# Alfa_t.net
KiCad netlist of a schematic drawn in EAGLE
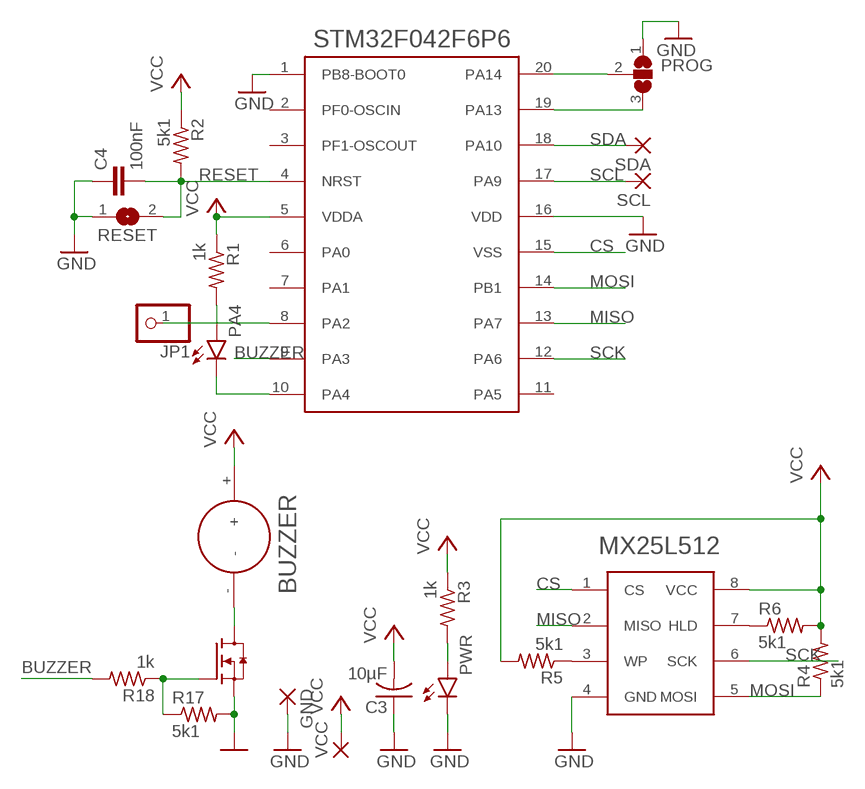
[diagram p0: schematic, sheet 1]

(export (version "E")
  (design (tool "Eeschema 10.0.6"))
  (components
    (comp (ref "BUZ")
      (value "SI2302CDS")
      (footprint "eagle-import:SOT23-3")
      (libsource (lib "eagle-import") (part "SI2302CDS"))
    )
    (comp (ref "BUZZER")
      (value "BUZZER-5V")
      (footprint "eagle-import:BUZZER")
      (libsource (lib "eagle-import") (part "BUZZER-5V"))
    )
    (comp (ref "C3")
      (value "10µF")
      (footprint "eagle-import:C1206")
      (libsource (lib "eagle-import") (part "C-USC1206"))
    )
    (comp (ref "C4")
      (value "100nF")
      (footprint "eagle-import:C0603")
      (libsource (lib "eagle-import") (part "C-EUC0603"))
    )
    (comp (ref "GND")
      (value "SMD2")
      (footprint "eagle-import:SMD1,27-2,54")
      (libsource (lib "eagle-import") (part "SMD2"))
    )
    (comp (ref "JP1")
      (value "PINHD-1X1")
      (footprint "eagle-import:1X01")
      (libsource (lib "eagle-import") (part "PINHD-1X1"))
    )
    (comp (ref "MX25L512")
      (value "MX25L25645")
      (footprint "eagle-import:SOP8")
      (libsource (lib "eagle-import") (part "MX25L25645"))
    )
    (comp (ref "PA4")
      (value "LEDCHIPLED_0603")
      (footprint "eagle-import:CHIPLED_0603")
      (libsource (lib "eagle-import") (part "LEDCHIPLED_0603"))
    )
    (comp (ref "PROG")
      (value "SJ2W")
      (footprint "eagle-import:SJ_2")
      (libsource (lib "eagle-import") (part "SJ2W"))
    )
    (comp (ref "PWR")
      (value "LEDCHIPLED_0603")
      (footprint "eagle-import:CHIPLED_0603")
      (libsource (lib "eagle-import") (part "LEDCHIPLED_0603"))
    )
    (comp (ref "R1")
      (value "1k")
      (footprint "eagle-import:R0603")
      (libsource (lib "eagle-import") (part "R-US_R0603"))
    )
    (comp (ref "R2")
      (value "5k1")
      (footprint "eagle-import:R0603")
      (libsource (lib "eagle-import") (part "R-US_R0603"))
    )
    (comp (ref "R3")
      (value "1k")
      (footprint "eagle-import:R0603")
      (libsource (lib "eagle-import") (part "R-US_R0603"))
    )
    (comp (ref "R4")
      (value "5k1")
      (footprint "eagle-import:R0603")
      (libsource (lib "eagle-import") (part "R-US_R0603"))
    )
    (comp (ref "R5")
      (value "5k1")
      (footprint "eagle-import:R0603")
      (libsource (lib "eagle-import") (part "R-US_R0603"))
    )
    (comp (ref "R6")
      (value "5k1")
      (footprint "eagle-import:R0603")
      (libsource (lib "eagle-import") (part "R-US_R0603"))
    )
    (comp (ref "R17")
      (value "5k1")
      (footprint "eagle-import:R0603")
      (libsource (lib "eagle-import") (part "R-US_R0603"))
    )
    (comp (ref "R18")
      (value "1k")
      (footprint "eagle-import:R0603")
      (libsource (lib "eagle-import") (part "R-US_R0603"))
    )
    (comp (ref "RESET")
      (value "SJ")
      (footprint "eagle-import:SJ")
      (libsource (lib "eagle-import") (part "SJ"))
    )
    (comp (ref "SCL")
      (value "SMD2")
      (footprint "eagle-import:SMD1,27-2,54")
      (libsource (lib "eagle-import") (part "SMD2"))
    )
    (comp (ref "SDA")
      (value "SMD2")
      (footprint "eagle-import:SMD1,27-2,54")
      (libsource (lib "eagle-import") (part "SMD2"))
    )
    (comp (ref "STM32F042F6P6")
      (value "STM32F042F6P6")
      (footprint "eagle-import:TSSOP-20")
      (libsource (lib "eagle-import") (part "STM32F042F6P6"))
    )
    (comp (ref "VCC")
      (value "SMD2")
      (footprint "eagle-import:SMD1,27-2,54")
      (libsource (lib "eagle-import") (part "SMD2"))
    )
  )
  (nets
    (net (code "1") (name "/BUZZER") (class "Default")
      (node (ref "R18") (pin "2") (pinfunction "2_2") (pintype "passive"))
      (node (ref "STM32F042F6P6") (pin "9") (pinfunction "PA3_9") (pintype "bidirectional"))
    )
    (net (code "2") (name "/CS") (class "Default")
      (node (ref "MX25L512") (pin "1") (pinfunction "CS_1") (pintype "bidirectional"))
      (node (ref "STM32F042F6P6") (pin "15") (pinfunction "VSS_15") (pintype "bidirectional"))
    )
    (net (code "3") (name "/MISO") (class "Default")
      (node (ref "MX25L512") (pin "2") (pinfunction "MISO_2") (pintype "bidirectional"))
      (node (ref "STM32F042F6P6") (pin "13") (pinfunction "PA7_13") (pintype "bidirectional"))
    )
    (net (code "4") (name "/MOSI") (class "Default")
      (node (ref "MX25L512") (pin "5") (pinfunction "MOSI_5") (pintype "bidirectional"))
      (node (ref "R4") (pin "1") (pinfunction "1_1") (pintype "passive"))
      (node (ref "STM32F042F6P6") (pin "14") (pinfunction "PB1_14") (pintype "bidirectional"))
    )
    (net (code "5") (name "/RESET") (class "Default")
      (node (ref "C4") (pin "2") (pinfunction "2_2") (pintype "passive"))
      (node (ref "R2") (pin "2") (pinfunction "2_2") (pintype "passive"))
      (node (ref "RESET") (pin "2") (pinfunction "2_2") (pintype "passive"))
      (node (ref "STM32F042F6P6") (pin "4") (pinfunction "NRST_4") (pintype "bidirectional"))
    )
    (net (code "6") (name "/SCK") (class "Default")
      (node (ref "MX25L512") (pin "6") (pinfunction "SCK_6") (pintype "bidirectional"))
      (node (ref "STM32F042F6P6") (pin "12") (pinfunction "PA6_12") (pintype "bidirectional"))
    )
    (net (code "7") (name "/SCL") (class "Default")
      (node (ref "SCL") (pin "1") (pinfunction "P_1") (pintype "passive"))
      (node (ref "STM32F042F6P6") (pin "17") (pinfunction "PA9_17") (pintype "bidirectional"))
    )
    (net (code "8") (name "/SDA") (class "Default")
      (node (ref "SDA") (pin "1") (pinfunction "P_1") (pintype "passive"))
      (node (ref "STM32F042F6P6") (pin "18") (pinfunction "PA10_18") (pintype "bidirectional"))
    )
    (net (code "9") (name "GND") (class "Default")
      (node (ref "BUZ") (pin "2") (pinfunction "S_2") (pintype "passive"))
      (node (ref "C3") (pin "1") (pinfunction "1_1") (pintype "passive"))
      (node (ref "C4") (pin "1") (pinfunction "1_1") (pintype "passive"))
      (node (ref "GND") (pin "1") (pinfunction "P_1") (pintype "passive"))
      (node (ref "MX25L512") (pin "4") (pinfunction "GND_4") (pintype "bidirectional"))
      (node (ref "PROG") (pin "1") (pinfunction "1_1") (pintype "passive"))
      (node (ref "PWR") (pin "C") (pinfunction "C_C") (pintype "passive"))
      (node (ref "R17") (pin "2") (pinfunction "2_2") (pintype "passive"))
      (node (ref "RESET") (pin "1") (pinfunction "1_1") (pintype "passive"))
      (node (ref "STM32F042F6P6") (pin "1") (pinfunction "PB8-BOOT0_1") (pintype "bidirectional"))
      (node (ref "STM32F042F6P6") (pin "16") (pinfunction "VDD_16") (pintype "bidirectional"))
    )
    (net (code "10") (name "Net-(BUZ-D)") (class "Default")
      (node (ref "BUZ") (pin "3") (pinfunction "D_3") (pintype "passive"))
      (node (ref "BUZZER") (pin "-") (pinfunction "-_-") (pintype "bidirectional"))
    )
    (net (code "11") (name "Net-(BUZ-G)") (class "Default")
      (node (ref "BUZ") (pin "1") (pinfunction "G_1") (pintype "passive"))
      (node (ref "R17") (pin "1") (pinfunction "1_1") (pintype "passive"))
      (node (ref "R18") (pin "1") (pinfunction "1_1") (pintype "passive"))
    )
    (net (code "12") (name "Net-(MX25L512-HLD)") (class "Default")
      (node (ref "MX25L512") (pin "7") (pinfunction "HLD_7") (pintype "bidirectional"))
      (node (ref "R6") (pin "1") (pinfunction "1_1") (pintype "passive"))
    )
    (net (code "13") (name "Net-(MX25L512-WP)") (class "Default")
      (node (ref "MX25L512") (pin "3") (pinfunction "WP_3") (pintype "bidirectional"))
      (node (ref "R5") (pin "1") (pinfunction "1_1") (pintype "passive"))
    )
    (net (code "14") (name "Net-(PA4-PadA)") (class "Default")
      (node (ref "PA4") (pin "A") (pinfunction "A_A") (pintype "passive"))
      (node (ref "R1") (pin "2") (pinfunction "2_2") (pintype "passive"))
    )
    (net (code "15") (name "Net-(PWR-PadA)") (class "Default")
      (node (ref "PWR") (pin "A") (pinfunction "A_A") (pintype "passive"))
      (node (ref "R3") (pin "2") (pinfunction "2_2") (pintype "passive"))
    )
    (net (code "16") (name "Net-(STM32F042F6P6-PA2)") (class "Default")
      (node (ref "JP1") (pin "1") (pinfunction "1_1") (pintype "passive"))
      (node (ref "STM32F042F6P6") (pin "8") (pinfunction "PA2_8") (pintype "bidirectional"))
    )
    (net (code "17") (name "Net-(STM32F042F6P6-PA4)") (class "Default")
      (node (ref "PA4") (pin "C") (pinfunction "C_C") (pintype "passive"))
      (node (ref "STM32F042F6P6") (pin "10") (pinfunction "PA4_10") (pintype "bidirectional"))
    )
    (net (code "18") (name "Net-(STM32F042F6P6-PA13)") (class "Default")
      (node (ref "PROG") (pin "3") (pinfunction "3_3") (pintype "passive"))
      (node (ref "STM32F042F6P6") (pin "19") (pinfunction "PA13_19") (pintype "bidirectional"))
    )
    (net (code "19") (name "Net-(STM32F042F6P6-PA14)") (class "Default")
      (node (ref "PROG") (pin "2") (pinfunction "2_2") (pintype "passive"))
      (node (ref "STM32F042F6P6") (pin "20") (pinfunction "PA14_20") (pintype "bidirectional"))
    )
    (net (code "20") (name "VCC") (class "Default")
      (node (ref "BUZZER") (pin "+") (pinfunction "+_+") (pintype "bidirectional"))
      (node (ref "C3") (pin "2") (pinfunction "2_2") (pintype "passive"))
      (node (ref "MX25L512") (pin "8") (pinfunction "VCC_8") (pintype "bidirectional"))
      (node (ref "R1") (pin "1") (pinfunction "1_1") (pintype "passive"))
      (node (ref "R2") (pin "1") (pinfunction "1_1") (pintype "passive"))
      (node (ref "R3") (pin "1") (pinfunction "1_1") (pintype "passive"))
      (node (ref "R4") (pin "2") (pinfunction "2_2") (pintype "passive"))
      (node (ref "R5") (pin "2") (pinfunction "2_2") (pintype "passive"))
      (node (ref "R6") (pin "2") (pinfunction "2_2") (pintype "passive"))
      (node (ref "STM32F042F6P6") (pin "5") (pinfunction "VDDA_5") (pintype "bidirectional"))
      (node (ref "VCC") (pin "1") (pinfunction "P_1") (pintype "passive"))
    )
    (net (code "21") (name "unconnected-(STM32F042F6P6-PA0-Pad6)") (class "Default")
      (node (ref "STM32F042F6P6") (pin "6") (pinfunction "PA0_6") (pintype "bidirectional"))
    )
    (net (code "22") (name "unconnected-(STM32F042F6P6-PA1-Pad7)") (class "Default")
      (node (ref "STM32F042F6P6") (pin "7") (pinfunction "PA1_7") (pintype "bidirectional"))
    )
    (net (code "23") (name "unconnected-(STM32F042F6P6-PA5-Pad11)") (class "Default")
      (node (ref "STM32F042F6P6") (pin "11") (pinfunction "PA5_11") (pintype "bidirectional"))
    )
    (net (code "24") (name "unconnected-(STM32F042F6P6-PF0-OSCIN-Pad2)") (class "Default")
      (node (ref "STM32F042F6P6") (pin "2") (pinfunction "PF0-OSCIN_2") (pintype "bidirectional"))
    )
    (net (code "25") (name "unconnected-(STM32F042F6P6-PF1-OSCOUT-Pad3)") (class "Default")
      (node (ref "STM32F042F6P6") (pin "3") (pinfunction "PF1-OSCOUT_3") (pintype "bidirectional"))
    )
  )
)
